# actuatorBoard_2.net
KiCad netlist of a schematic drawn in EAGLE
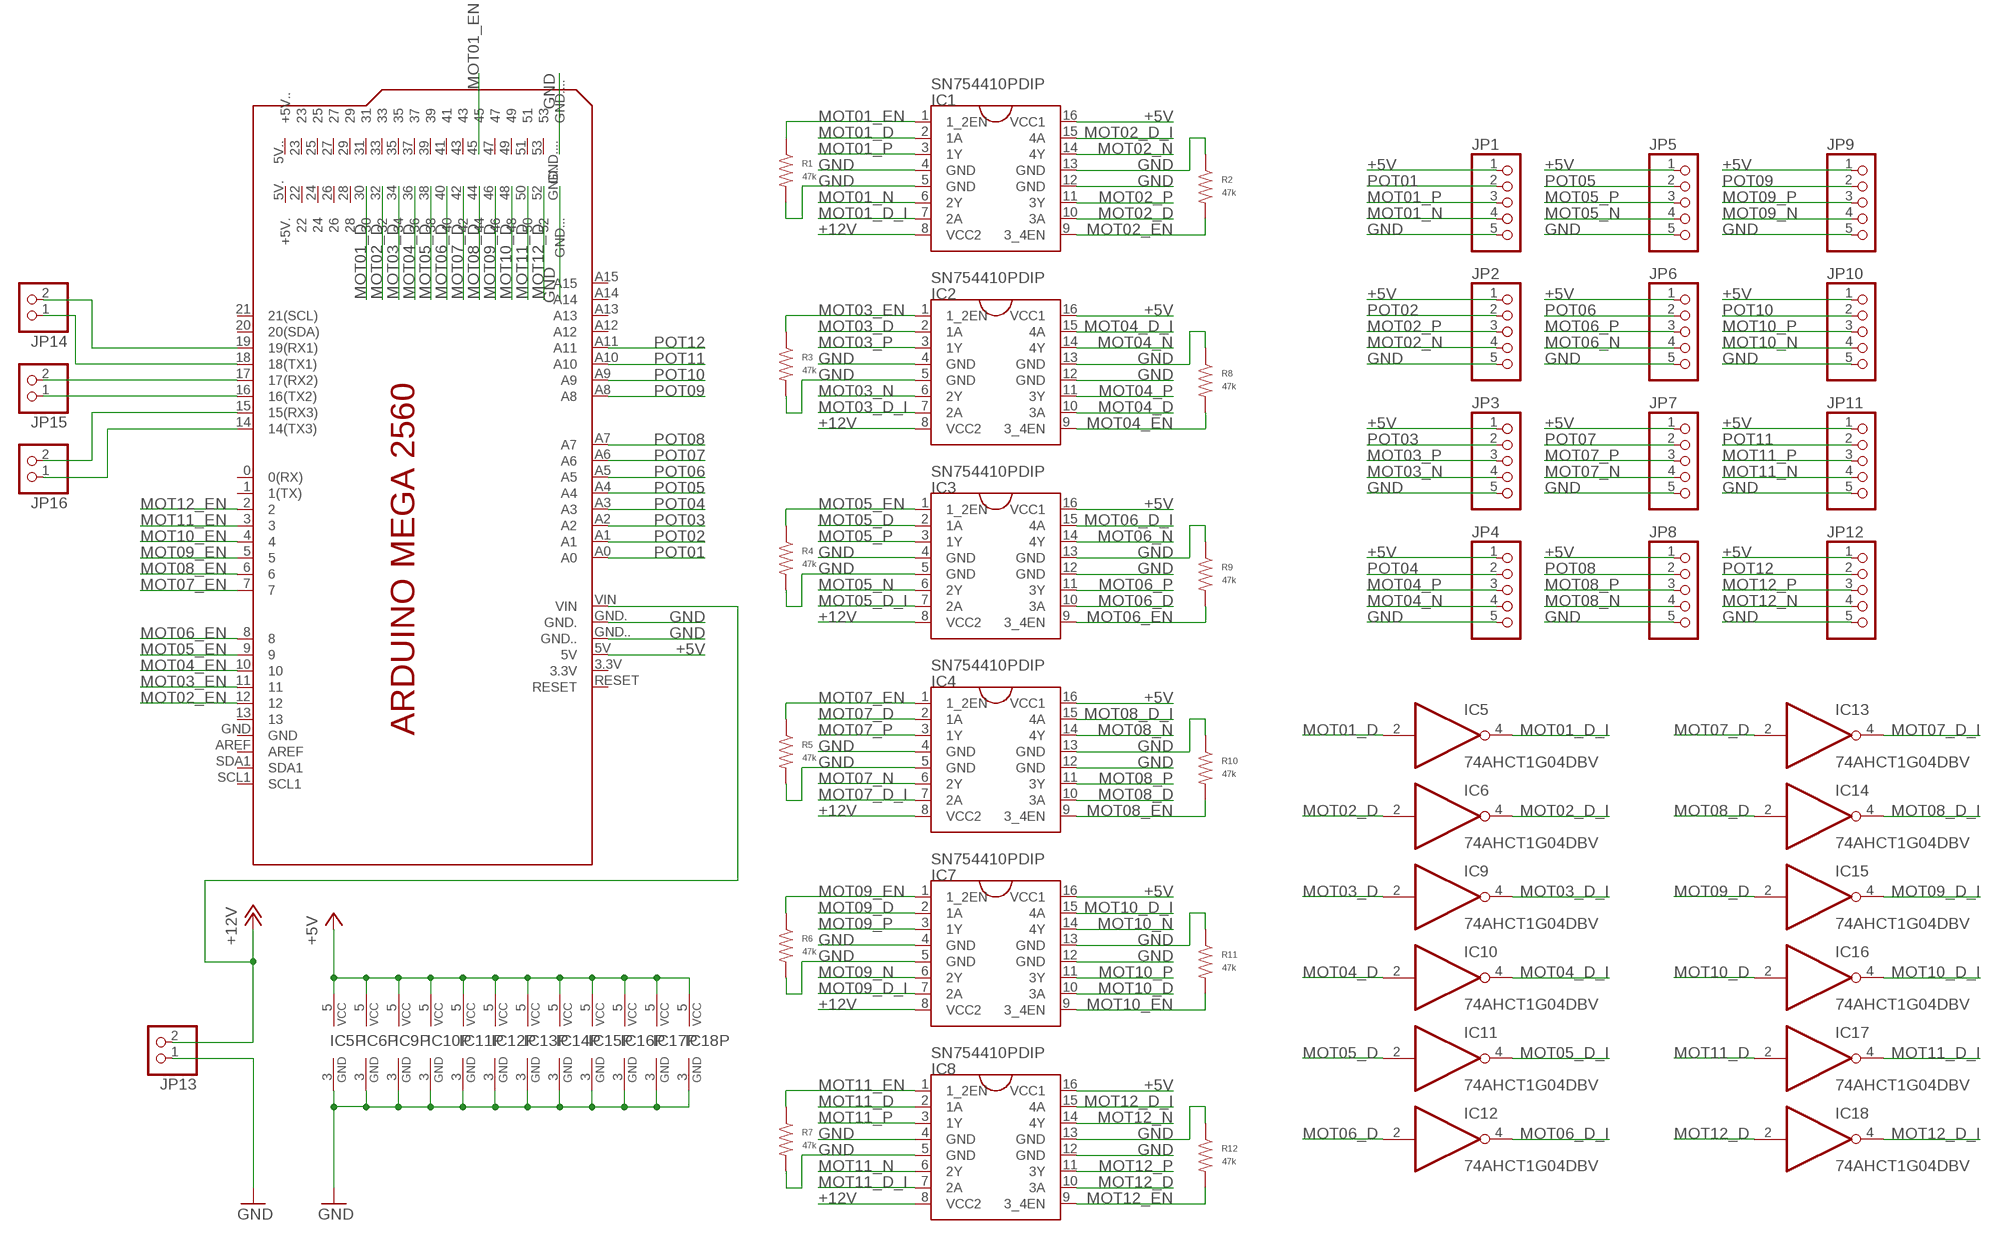
[diagram p0: schematic, sheet 1]

(export (version "E")
  (design (tool "Eeschema 10.0.6"))
  (components
    (comp (ref "IC1")
      (value "SN754410PDIP")
      (footprint "eagle-import:DIL16")
      (libsource (lib "eagle-import") (part "SN754410PDIP"))
    )
    (comp (ref "IC2")
      (value "SN754410PDIP")
      (footprint "eagle-import:DIL16")
      (libsource (lib "eagle-import") (part "SN754410PDIP"))
    )
    (comp (ref "IC3")
      (value "SN754410PDIP")
      (footprint "eagle-import:DIL16")
      (libsource (lib "eagle-import") (part "SN754410PDIP"))
    )
    (comp (ref "IC4")
      (value "SN754410PDIP")
      (footprint "eagle-import:DIL16")
      (libsource (lib "eagle-import") (part "SN754410PDIP"))
    )
    (comp (ref "IC5")
      (value "74AHCT1G04DBV")
      (footprint "eagle-import:SOT23-5")
      (libsource (lib "eagle-import") (part "741G04DBVAHCT"))
    )
    (comp (ref "IC6")
      (value "74AHCT1G04DBV")
      (footprint "eagle-import:SOT23-5")
      (libsource (lib "eagle-import") (part "741G04DBVAHCT"))
    )
    (comp (ref "IC7")
      (value "SN754410PDIP")
      (footprint "eagle-import:DIL16")
      (libsource (lib "eagle-import") (part "SN754410PDIP"))
    )
    (comp (ref "IC8")
      (value "SN754410PDIP")
      (footprint "eagle-import:DIL16")
      (libsource (lib "eagle-import") (part "SN754410PDIP"))
    )
    (comp (ref "IC9")
      (value "74AHCT1G04DBV")
      (footprint "eagle-import:SOT23-5")
      (libsource (lib "eagle-import") (part "741G04DBVAHCT"))
    )
    (comp (ref "IC10")
      (value "74AHCT1G04DBV")
      (footprint "eagle-import:SOT23-5")
      (libsource (lib "eagle-import") (part "741G04DBVAHCT"))
    )
    (comp (ref "IC11")
      (value "74AHCT1G04DBV")
      (footprint "eagle-import:SOT23-5")
      (libsource (lib "eagle-import") (part "741G04DBVAHCT"))
    )
    (comp (ref "IC12")
      (value "74AHCT1G04DBV")
      (footprint "eagle-import:SOT23-5")
      (libsource (lib "eagle-import") (part "741G04DBVAHCT"))
    )
    (comp (ref "IC13")
      (value "74AHCT1G04DBV")
      (footprint "eagle-import:SOT23-5")
      (libsource (lib "eagle-import") (part "741G04DBVAHCT"))
    )
    (comp (ref "IC14")
      (value "74AHCT1G04DBV")
      (footprint "eagle-import:SOT23-5")
      (libsource (lib "eagle-import") (part "741G04DBVAHCT"))
    )
    (comp (ref "IC15")
      (value "74AHCT1G04DBV")
      (footprint "eagle-import:SOT23-5")
      (libsource (lib "eagle-import") (part "741G04DBVAHCT"))
    )
    (comp (ref "IC16")
      (value "74AHCT1G04DBV")
      (footprint "eagle-import:SOT23-5")
      (libsource (lib "eagle-import") (part "741G04DBVAHCT"))
    )
    (comp (ref "IC17")
      (value "74AHCT1G04DBV")
      (footprint "eagle-import:SOT23-5")
      (libsource (lib "eagle-import") (part "741G04DBVAHCT"))
    )
    (comp (ref "IC18")
      (value "74AHCT1G04DBV")
      (footprint "eagle-import:SOT23-5")
      (libsource (lib "eagle-import") (part "741G04DBVAHCT"))
    )
    (comp (ref "JP1")
      (value "PINHD-1X5")
      (footprint "eagle-import:1X05")
      (libsource (lib "eagle-import") (part "PINHD-1X5"))
    )
    (comp (ref "JP2")
      (value "PINHD-1X5")
      (footprint "eagle-import:1X05")
      (libsource (lib "eagle-import") (part "PINHD-1X5"))
    )
    (comp (ref "JP3")
      (value "PINHD-1X5")
      (footprint "eagle-import:1X05")
      (libsource (lib "eagle-import") (part "PINHD-1X5"))
    )
    (comp (ref "JP4")
      (value "PINHD-1X5")
      (footprint "eagle-import:1X05")
      (libsource (lib "eagle-import") (part "PINHD-1X5"))
    )
    (comp (ref "JP5")
      (value "PINHD-1X5")
      (footprint "eagle-import:1X05")
      (libsource (lib "eagle-import") (part "PINHD-1X5"))
    )
    (comp (ref "JP6")
      (value "PINHD-1X5")
      (footprint "eagle-import:1X05")
      (libsource (lib "eagle-import") (part "PINHD-1X5"))
    )
    (comp (ref "JP7")
      (value "PINHD-1X5")
      (footprint "eagle-import:1X05")
      (libsource (lib "eagle-import") (part "PINHD-1X5"))
    )
    (comp (ref "JP8")
      (value "PINHD-1X5")
      (footprint "eagle-import:1X05")
      (libsource (lib "eagle-import") (part "PINHD-1X5"))
    )
    (comp (ref "JP9")
      (value "PINHD-1X5")
      (footprint "eagle-import:1X05")
      (libsource (lib "eagle-import") (part "PINHD-1X5"))
    )
    (comp (ref "JP10")
      (value "PINHD-1X5")
      (footprint "eagle-import:1X05")
      (libsource (lib "eagle-import") (part "PINHD-1X5"))
    )
    (comp (ref "JP11")
      (value "PINHD-1X5")
      (footprint "eagle-import:1X05")
      (libsource (lib "eagle-import") (part "PINHD-1X5"))
    )
    (comp (ref "JP12")
      (value "PINHD-1X5")
      (footprint "eagle-import:1X05")
      (libsource (lib "eagle-import") (part "PINHD-1X5"))
    )
    (comp (ref "JP13")
      (value "PINHD-1X2")
      (footprint "eagle-import:1X02")
      (libsource (lib "eagle-import") (part "PINHD-1X2"))
    )
    (comp (ref "JP14")
      (value "PINHD-1X2")
      (footprint "eagle-import:1X02")
      (libsource (lib "eagle-import") (part "PINHD-1X2"))
    )
    (comp (ref "JP15")
      (value "PINHD-1X2")
      (footprint "eagle-import:1X02")
      (libsource (lib "eagle-import") (part "PINHD-1X2"))
    )
    (comp (ref "JP16")
      (value "PINHD-1X2")
      (footprint "eagle-import:1X02")
      (libsource (lib "eagle-import") (part "PINHD-1X2"))
    )
    (comp (ref "PCB1")
      (value "ARDUINO_MEGA2560")
      (footprint "eagle-import:ARDUINO_MEGA2560")
      (libsource (lib "eagle-import") (part "ARDUINO_MEGA2560"))
    )
    (comp (ref "R1")
      (value "47k")
      (footprint "eagle-import:R0603")
      (libsource (lib "eagle-import") (part "RESISTOR_0603"))
    )
    (comp (ref "R2")
      (value "47k")
      (footprint "eagle-import:R0603")
      (libsource (lib "eagle-import") (part "RESISTOR_0603"))
    )
    (comp (ref "R3")
      (value "47k")
      (footprint "eagle-import:R0603")
      (libsource (lib "eagle-import") (part "RESISTOR_0603"))
    )
    (comp (ref "R4")
      (value "47k")
      (footprint "eagle-import:R0603")
      (libsource (lib "eagle-import") (part "RESISTOR_0603"))
    )
    (comp (ref "R5")
      (value "47k")
      (footprint "eagle-import:R0603")
      (libsource (lib "eagle-import") (part "RESISTOR_0603"))
    )
    (comp (ref "R6")
      (value "47k")
      (footprint "eagle-import:R0603")
      (libsource (lib "eagle-import") (part "RESISTOR_0603"))
    )
    (comp (ref "R7")
      (value "47k")
      (footprint "eagle-import:R0603")
      (libsource (lib "eagle-import") (part "RESISTOR_0603"))
    )
    (comp (ref "R8")
      (value "47k")
      (footprint "eagle-import:R0603")
      (libsource (lib "eagle-import") (part "RESISTOR_0603"))
    )
    (comp (ref "R9")
      (value "47k")
      (footprint "eagle-import:R0603")
      (libsource (lib "eagle-import") (part "RESISTOR_0603"))
    )
    (comp (ref "R10")
      (value "47k")
      (footprint "eagle-import:R0603")
      (libsource (lib "eagle-import") (part "RESISTOR_0603"))
    )
    (comp (ref "R11")
      (value "47k")
      (footprint "eagle-import:R0603")
      (libsource (lib "eagle-import") (part "RESISTOR_0603"))
    )
    (comp (ref "R12")
      (value "47k")
      (footprint "eagle-import:R0603")
      (libsource (lib "eagle-import") (part "RESISTOR_0603"))
    )
  )
  (nets
    (net (code "1") (name "+5V") (class "Default")
      (node (ref "IC1") (pin "16") (pinfunction "VCC1_16") (pintype "bidirectional"))
      (node (ref "IC10") (pin "5") (pinfunction "VCC_5") (pintype "power_in"))
      (node (ref "IC11") (pin "5") (pinfunction "VCC_5") (pintype "power_in"))
      (node (ref "IC12") (pin "5") (pinfunction "VCC_5") (pintype "power_in"))
      (node (ref "IC13") (pin "5") (pinfunction "VCC_5") (pintype "power_in"))
      (node (ref "IC14") (pin "5") (pinfunction "VCC_5") (pintype "power_in"))
      (node (ref "IC15") (pin "5") (pinfunction "VCC_5") (pintype "power_in"))
      (node (ref "IC16") (pin "5") (pinfunction "VCC_5") (pintype "power_in"))
      (node (ref "IC17") (pin "5") (pinfunction "VCC_5") (pintype "power_in"))
      (node (ref "IC18") (pin "5") (pinfunction "VCC_5") (pintype "power_in"))
      (node (ref "IC2") (pin "16") (pinfunction "VCC1_16") (pintype "bidirectional"))
      (node (ref "IC3") (pin "16") (pinfunction "VCC1_16") (pintype "bidirectional"))
      (node (ref "IC4") (pin "16") (pinfunction "VCC1_16") (pintype "bidirectional"))
      (node (ref "IC5") (pin "5") (pinfunction "VCC_5") (pintype "power_in"))
      (node (ref "IC6") (pin "5") (pinfunction "VCC_5") (pintype "power_in"))
      (node (ref "IC7") (pin "16") (pinfunction "VCC1_16") (pintype "bidirectional"))
      (node (ref "IC8") (pin "16") (pinfunction "VCC1_16") (pintype "bidirectional"))
      (node (ref "IC9") (pin "5") (pinfunction "VCC_5") (pintype "power_in"))
      (node (ref "JP1") (pin "1") (pinfunction "1_1") (pintype "passive"))
      (node (ref "JP10") (pin "1") (pinfunction "1_1") (pintype "passive"))
      (node (ref "JP11") (pin "1") (pinfunction "1_1") (pintype "passive"))
      (node (ref "JP12") (pin "1") (pinfunction "1_1") (pintype "passive"))
      (node (ref "JP2") (pin "1") (pinfunction "1_1") (pintype "passive"))
      (node (ref "JP3") (pin "1") (pinfunction "1_1") (pintype "passive"))
      (node (ref "JP4") (pin "1") (pinfunction "1_1") (pintype "passive"))
      (node (ref "JP5") (pin "1") (pinfunction "1_1") (pintype "passive"))
      (node (ref "JP6") (pin "1") (pinfunction "1_1") (pintype "passive"))
      (node (ref "JP7") (pin "1") (pinfunction "1_1") (pintype "passive"))
      (node (ref "JP8") (pin "1") (pinfunction "1_1") (pintype "passive"))
      (node (ref "JP9") (pin "1") (pinfunction "1_1") (pintype "passive"))
      (node (ref "PCB1") (pin "5V") (pinfunction "5V_5V") (pintype "bidirectional"))
    )
    (net (code "2") (name "+12V") (class "Default")
      (node (ref "IC1") (pin "8") (pinfunction "VCC2_8") (pintype "bidirectional"))
      (node (ref "IC2") (pin "8") (pinfunction "VCC2_8") (pintype "bidirectional"))
      (node (ref "IC3") (pin "8") (pinfunction "VCC2_8") (pintype "bidirectional"))
      (node (ref "IC4") (pin "8") (pinfunction "VCC2_8") (pintype "bidirectional"))
      (node (ref "IC7") (pin "8") (pinfunction "VCC2_8") (pintype "bidirectional"))
      (node (ref "IC8") (pin "8") (pinfunction "VCC2_8") (pintype "bidirectional"))
      (node (ref "JP13") (pin "2") (pinfunction "2_2") (pintype "passive"))
      (node (ref "PCB1") (pin "VIN") (pinfunction "VIN_VIN") (pintype "bidirectional"))
    )
    (net (code "3") (name "/MOT01_D") (class "Default")
      (node (ref "IC1") (pin "2") (pinfunction "1A_2") (pintype "bidirectional"))
      (node (ref "IC5") (pin "2") (pinfunction "I_2") (pintype "input"))
      (node (ref "PCB1") (pin "30") (pinfunction "30_30") (pintype "bidirectional"))
    )
    (net (code "4") (name "/MOT01_D_I") (class "Default")
      (node (ref "IC1") (pin "7") (pinfunction "2A_7") (pintype "bidirectional"))
      (node (ref "IC5") (pin "4") (pinfunction "O_4") (pintype "output"))
    )
    (net (code "5") (name "/MOT01_EN") (class "Default")
      (node (ref "IC1") (pin "1") (pinfunction "1_2EN_1") (pintype "bidirectional"))
      (node (ref "PCB1") (pin "45") (pinfunction "45_45") (pintype "bidirectional"))
      (node (ref "R1") (pin "P$1") (pinfunction "P$1_P$1") (pintype "passive"))
    )
    (net (code "6") (name "/MOT01_N") (class "Default")
      (node (ref "IC1") (pin "6") (pinfunction "2Y_6") (pintype "bidirectional"))
      (node (ref "JP1") (pin "4") (pinfunction "4_4") (pintype "passive"))
    )
    (net (code "7") (name "/MOT01_P") (class "Default")
      (node (ref "IC1") (pin "3") (pinfunction "1Y_3") (pintype "bidirectional"))
      (node (ref "JP1") (pin "3") (pinfunction "3_3") (pintype "passive"))
    )
    (net (code "8") (name "/MOT02_D") (class "Default")
      (node (ref "IC1") (pin "10") (pinfunction "3A_10") (pintype "bidirectional"))
      (node (ref "IC6") (pin "2") (pinfunction "I_2") (pintype "input"))
      (node (ref "PCB1") (pin "32") (pinfunction "32_32") (pintype "bidirectional"))
    )
    (net (code "9") (name "/MOT02_D_I") (class "Default")
      (node (ref "IC1") (pin "15") (pinfunction "4A_15") (pintype "bidirectional"))
      (node (ref "IC6") (pin "4") (pinfunction "O_4") (pintype "output"))
    )
    (net (code "10") (name "/MOT02_EN") (class "Default")
      (node (ref "IC1") (pin "9") (pinfunction "3_4EN_9") (pintype "bidirectional"))
      (node (ref "PCB1") (pin "12") (pinfunction "12_12") (pintype "bidirectional"))
      (node (ref "R2") (pin "P$2") (pinfunction "P$2_P$2") (pintype "passive"))
    )
    (net (code "11") (name "/MOT02_N") (class "Default")
      (node (ref "IC1") (pin "14") (pinfunction "4Y_14") (pintype "bidirectional"))
      (node (ref "JP2") (pin "4") (pinfunction "4_4") (pintype "passive"))
    )
    (net (code "12") (name "/MOT02_P") (class "Default")
      (node (ref "IC1") (pin "11") (pinfunction "3Y_11") (pintype "bidirectional"))
      (node (ref "JP2") (pin "3") (pinfunction "3_3") (pintype "passive"))
    )
    (net (code "13") (name "/MOT03_D") (class "Default")
      (node (ref "IC2") (pin "2") (pinfunction "1A_2") (pintype "bidirectional"))
      (node (ref "IC9") (pin "2") (pinfunction "I_2") (pintype "input"))
      (node (ref "PCB1") (pin "34") (pinfunction "34_34") (pintype "bidirectional"))
    )
    (net (code "14") (name "/MOT03_D_I") (class "Default")
      (node (ref "IC2") (pin "7") (pinfunction "2A_7") (pintype "bidirectional"))
      (node (ref "IC9") (pin "4") (pinfunction "O_4") (pintype "output"))
    )
    (net (code "15") (name "/MOT03_EN") (class "Default")
      (node (ref "IC2") (pin "1") (pinfunction "1_2EN_1") (pintype "bidirectional"))
      (node (ref "PCB1") (pin "11") (pinfunction "11_11") (pintype "bidirectional"))
      (node (ref "R3") (pin "P$1") (pinfunction "P$1_P$1") (pintype "passive"))
    )
    (net (code "16") (name "/MOT03_N") (class "Default")
      (node (ref "IC2") (pin "6") (pinfunction "2Y_6") (pintype "bidirectional"))
      (node (ref "JP3") (pin "4") (pinfunction "4_4") (pintype "passive"))
    )
    (net (code "17") (name "/MOT03_P") (class "Default")
      (node (ref "IC2") (pin "3") (pinfunction "1Y_3") (pintype "bidirectional"))
      (node (ref "JP3") (pin "3") (pinfunction "3_3") (pintype "passive"))
    )
    (net (code "18") (name "/MOT04_D") (class "Default")
      (node (ref "IC10") (pin "2") (pinfunction "I_2") (pintype "input"))
      (node (ref "IC2") (pin "10") (pinfunction "3A_10") (pintype "bidirectional"))
      (node (ref "PCB1") (pin "36") (pinfunction "36_36") (pintype "bidirectional"))
    )
    (net (code "19") (name "/MOT04_D_I") (class "Default")
      (node (ref "IC10") (pin "4") (pinfunction "O_4") (pintype "output"))
      (node (ref "IC2") (pin "15") (pinfunction "4A_15") (pintype "bidirectional"))
    )
    (net (code "20") (name "/MOT04_EN") (class "Default")
      (node (ref "IC2") (pin "9") (pinfunction "3_4EN_9") (pintype "bidirectional"))
      (node (ref "PCB1") (pin "10") (pinfunction "10_10") (pintype "bidirectional"))
      (node (ref "R8") (pin "P$2") (pinfunction "P$2_P$2") (pintype "passive"))
    )
    (net (code "21") (name "/MOT04_N") (class "Default")
      (node (ref "IC2") (pin "14") (pinfunction "4Y_14") (pintype "bidirectional"))
      (node (ref "JP4") (pin "4") (pinfunction "4_4") (pintype "passive"))
    )
    (net (code "22") (name "/MOT04_P") (class "Default")
      (node (ref "IC2") (pin "11") (pinfunction "3Y_11") (pintype "bidirectional"))
      (node (ref "JP4") (pin "3") (pinfunction "3_3") (pintype "passive"))
    )
    (net (code "23") (name "/MOT05_D") (class "Default")
      (node (ref "IC11") (pin "2") (pinfunction "I_2") (pintype "input"))
      (node (ref "IC3") (pin "2") (pinfunction "1A_2") (pintype "bidirectional"))
      (node (ref "PCB1") (pin "38") (pinfunction "38_38") (pintype "bidirectional"))
    )
    (net (code "24") (name "/MOT05_D_I") (class "Default")
      (node (ref "IC11") (pin "4") (pinfunction "O_4") (pintype "output"))
      (node (ref "IC3") (pin "7") (pinfunction "2A_7") (pintype "bidirectional"))
    )
    (net (code "25") (name "/MOT05_EN") (class "Default")
      (node (ref "IC3") (pin "1") (pinfunction "1_2EN_1") (pintype "bidirectional"))
      (node (ref "PCB1") (pin "9") (pinfunction "9_9") (pintype "bidirectional"))
      (node (ref "R4") (pin "P$1") (pinfunction "P$1_P$1") (pintype "passive"))
    )
    (net (code "26") (name "/MOT05_N") (class "Default")
      (node (ref "IC3") (pin "6") (pinfunction "2Y_6") (pintype "bidirectional"))
      (node (ref "JP5") (pin "4") (pinfunction "4_4") (pintype "passive"))
    )
    (net (code "27") (name "/MOT05_P") (class "Default")
      (node (ref "IC3") (pin "3") (pinfunction "1Y_3") (pintype "bidirectional"))
      (node (ref "JP5") (pin "3") (pinfunction "3_3") (pintype "passive"))
    )
    (net (code "28") (name "/MOT06_D") (class "Default")
      (node (ref "IC12") (pin "2") (pinfunction "I_2") (pintype "input"))
      (node (ref "IC3") (pin "10") (pinfunction "3A_10") (pintype "bidirectional"))
      (node (ref "PCB1") (pin "40") (pinfunction "40_40") (pintype "bidirectional"))
    )
    (net (code "29") (name "/MOT06_D_I") (class "Default")
      (node (ref "IC12") (pin "4") (pinfunction "O_4") (pintype "output"))
      (node (ref "IC3") (pin "15") (pinfunction "4A_15") (pintype "bidirectional"))
    )
    (net (code "30") (name "/MOT06_EN") (class "Default")
      (node (ref "IC3") (pin "9") (pinfunction "3_4EN_9") (pintype "bidirectional"))
      (node (ref "PCB1") (pin "8") (pinfunction "8_8") (pintype "bidirectional"))
      (node (ref "R9") (pin "P$2") (pinfunction "P$2_P$2") (pintype "passive"))
    )
    (net (code "31") (name "/MOT06_N") (class "Default")
      (node (ref "IC3") (pin "14") (pinfunction "4Y_14") (pintype "bidirectional"))
      (node (ref "JP6") (pin "4") (pinfunction "4_4") (pintype "passive"))
    )
    (net (code "32") (name "/MOT06_P") (class "Default")
      (node (ref "IC3") (pin "11") (pinfunction "3Y_11") (pintype "bidirectional"))
      (node (ref "JP6") (pin "3") (pinfunction "3_3") (pintype "passive"))
    )
    (net (code "33") (name "/MOT07_D") (class "Default")
      (node (ref "IC13") (pin "2") (pinfunction "I_2") (pintype "input"))
      (node (ref "IC4") (pin "2") (pinfunction "1A_2") (pintype "bidirectional"))
      (node (ref "PCB1") (pin "42") (pinfunction "42_42") (pintype "bidirectional"))
    )
    (net (code "34") (name "/MOT07_D_I") (class "Default")
      (node (ref "IC13") (pin "4") (pinfunction "O_4") (pintype "output"))
      (node (ref "IC4") (pin "7") (pinfunction "2A_7") (pintype "bidirectional"))
    )
    (net (code "35") (name "/MOT07_EN") (class "Default")
      (node (ref "IC4") (pin "1") (pinfunction "1_2EN_1") (pintype "bidirectional"))
      (node (ref "PCB1") (pin "7") (pinfunction "7_7") (pintype "bidirectional"))
      (node (ref "R5") (pin "P$1") (pinfunction "P$1_P$1") (pintype "passive"))
    )
    (net (code "36") (name "/MOT07_N") (class "Default")
      (node (ref "IC4") (pin "6") (pinfunction "2Y_6") (pintype "bidirectional"))
      (node (ref "JP7") (pin "4") (pinfunction "4_4") (pintype "passive"))
    )
    (net (code "37") (name "/MOT07_P") (class "Default")
      (node (ref "IC4") (pin "3") (pinfunction "1Y_3") (pintype "bidirectional"))
      (node (ref "JP7") (pin "3") (pinfunction "3_3") (pintype "passive"))
    )
    (net (code "38") (name "/MOT08_D") (class "Default")
      (node (ref "IC14") (pin "2") (pinfunction "I_2") (pintype "input"))
      (node (ref "IC4") (pin "10") (pinfunction "3A_10") (pintype "bidirectional"))
      (node (ref "PCB1") (pin "44") (pinfunction "44_44") (pintype "bidirectional"))
    )
    (net (code "39") (name "/MOT08_D_I") (class "Default")
      (node (ref "IC14") (pin "4") (pinfunction "O_4") (pintype "output"))
      (node (ref "IC4") (pin "15") (pinfunction "4A_15") (pintype "bidirectional"))
    )
    (net (code "40") (name "/MOT08_EN") (class "Default")
      (node (ref "IC4") (pin "9") (pinfunction "3_4EN_9") (pintype "bidirectional"))
      (node (ref "PCB1") (pin "6") (pinfunction "6_6") (pintype "bidirectional"))
      (node (ref "R10") (pin "P$2") (pinfunction "P$2_P$2") (pintype "passive"))
    )
    (net (code "41") (name "/MOT08_N") (class "Default")
      (node (ref "IC4") (pin "14") (pinfunction "4Y_14") (pintype "bidirectional"))
      (node (ref "JP8") (pin "4") (pinfunction "4_4") (pintype "passive"))
    )
    (net (code "42") (name "/MOT08_P") (class "Default")
      (node (ref "IC4") (pin "11") (pinfunction "3Y_11") (pintype "bidirectional"))
      (node (ref "JP8") (pin "3") (pinfunction "3_3") (pintype "passive"))
    )
    (net (code "43") (name "/MOT09_D") (class "Default")
      (node (ref "IC15") (pin "2") (pinfunction "I_2") (pintype "input"))
      (node (ref "IC7") (pin "2") (pinfunction "1A_2") (pintype "bidirectional"))
      (node (ref "PCB1") (pin "46") (pinfunction "46_46") (pintype "bidirectional"))
    )
    (net (code "44") (name "/MOT09_D_I") (class "Default")
      (node (ref "IC15") (pin "4") (pinfunction "O_4") (pintype "output"))
      (node (ref "IC7") (pin "7") (pinfunction "2A_7") (pintype "bidirectional"))
    )
    (net (code "45") (name "/MOT09_EN") (class "Default")
      (node (ref "IC7") (pin "1") (pinfunction "1_2EN_1") (pintype "bidirectional"))
      (node (ref "PCB1") (pin "5") (pinfunction "5_5") (pintype "bidirectional"))
      (node (ref "R6") (pin "P$1") (pinfunction "P$1_P$1") (pintype "passive"))
    )
    (net (code "46") (name "/MOT09_N") (class "Default")
      (node (ref "IC7") (pin "6") (pinfunction "2Y_6") (pintype "bidirectional"))
      (node (ref "JP9") (pin "4") (pinfunction "4_4") (pintype "passive"))
    )
    (net (code "47") (name "/MOT09_P") (class "Default")
      (node (ref "IC7") (pin "3") (pinfunction "1Y_3") (pintype "bidirectional"))
      (node (ref "JP9") (pin "3") (pinfunction "3_3") (pintype "passive"))
    )
    (net (code "48") (name "/MOT10_D") (class "Default")
      (node (ref "IC16") (pin "2") (pinfunction "I_2") (pintype "input"))
      (node (ref "IC7") (pin "10") (pinfunction "3A_10") (pintype "bidirectional"))
      (node (ref "PCB1") (pin "48") (pinfunction "48_48") (pintype "bidirectional"))
    )
    (net (code "49") (name "/MOT10_D_I") (class "Default")
      (node (ref "IC16") (pin "4") (pinfunction "O_4") (pintype "output"))
      (node (ref "IC7") (pin "15") (pinfunction "4A_15") (pintype "bidirectional"))
    )
    (net (code "50") (name "/MOT10_EN") (class "Default")
      (node (ref "IC7") (pin "9") (pinfunction "3_4EN_9") (pintype "bidirectional"))
      (node (ref "PCB1") (pin "4") (pinfunction "4_4") (pintype "bidirectional"))
      (node (ref "R11") (pin "P$2") (pinfunction "P$2_P$2") (pintype "passive"))
    )
    (net (code "51") (name "/MOT10_N") (class "Default")
      (node (ref "IC7") (pin "14") (pinfunction "4Y_14") (pintype "bidirectional"))
      (node (ref "JP10") (pin "4") (pinfunction "4_4") (pintype "passive"))
    )
    (net (code "52") (name "/MOT10_P") (class "Default")
      (node (ref "IC7") (pin "11") (pinfunction "3Y_11") (pintype "bidirectional"))
      (node (ref "JP10") (pin "3") (pinfunction "3_3") (pintype "passive"))
    )
    (net (code "53") (name "/MOT11_D") (class "Default")
      (node (ref "IC17") (pin "2") (pinfunction "I_2") (pintype "input"))
      (node (ref "IC8") (pin "2") (pinfunction "1A_2") (pintype "bidirectional"))
      (node (ref "PCB1") (pin "50") (pinfunction "50_50") (pintype "bidirectional"))
    )
    (net (code "54") (name "/MOT11_D_I") (class "Default")
      (node (ref "IC17") (pin "4") (pinfunction "O_4") (pintype "output"))
      (node (ref "IC8") (pin "7") (pinfunction "2A_7") (pintype "bidirectional"))
    )
    (net (code "55") (name "/MOT11_EN") (class "Default")
      (node (ref "IC8") (pin "1") (pinfunction "1_2EN_1") (pintype "bidirectional"))
      (node (ref "PCB1") (pin "3") (pinfunction "3_3") (pintype "bidirectional"))
      (node (ref "R7") (pin "P$1") (pinfunction "P$1_P$1") (pintype "passive"))
    )
    (net (code "56") (name "/MOT11_N") (class "Default")
      (node (ref "IC8") (pin "6") (pinfunction "2Y_6") (pintype "bidirectional"))
      (node (ref "JP11") (pin "4") (pinfunction "4_4") (pintype "passive"))
    )
    (net (code "57") (name "/MOT11_P") (class "Default")
      (node (ref "IC8") (pin "3") (pinfunction "1Y_3") (pintype "bidirectional"))
      (node (ref "JP11") (pin "3") (pinfunction "3_3") (pintype "passive"))
    )
    (net (code "58") (name "/MOT12_D") (class "Default")
      (node (ref "IC18") (pin "2") (pinfunction "I_2") (pintype "input"))
      (node (ref "IC8") (pin "10") (pinfunction "3A_10") (pintype "bidirectional"))
      (node (ref "PCB1") (pin "52") (pinfunction "52_52") (pintype "bidirectional"))
    )
    (net (code "59") (name "/MOT12_D_I") (class "Default")
      (node (ref "IC18") (pin "4") (pinfunction "O_4") (pintype "output"))
      (node (ref "IC8") (pin "15") (pinfunction "4A_15") (pintype "bidirectional"))
    )
    (net (code "60") (name "/MOT12_EN") (class "Default")
      (node (ref "IC8") (pin "9") (pinfunction "3_4EN_9") (pintype "bidirectional"))
      (node (ref "PCB1") (pin "2") (pinfunction "2_2") (pintype "bidirectional"))
      (node (ref "R12") (pin "P$2") (pinfunction "P$2_P$2") (pintype "passive"))
    )
    (net (code "61") (name "/MOT12_N") (class "Default")
      (node (ref "IC8") (pin "14") (pinfunction "4Y_14") (pintype "bidirectional"))
      (node (ref "JP12") (pin "4") (pinfunction "4_4") (pintype "passive"))
    )
    (net (code "62") (name "/MOT12_P") (class "Default")
      (node (ref "IC8") (pin "11") (pinfunction "3Y_11") (pintype "bidirectional"))
      (node (ref "JP12") (pin "3") (pinfunction "3_3") (pintype "passive"))
    )
    (net (code "63") (name "/POT01") (class "Default")
      (node (ref "JP1") (pin "2") (pinfunction "2_2") (pintype "passive"))
      (node (ref "PCB1") (pin "A0") (pinfunction "A0_A0") (pintype "bidirectional"))
    )
    (net (code "64") (name "/POT02") (class "Default")
      (node (ref "JP2") (pin "2") (pinfunction "2_2") (pintype "passive"))
      (node (ref "PCB1") (pin "A1") (pinfunction "A1_A1") (pintype "bidirectional"))
    )
    (net (code "65") (name "/POT03") (class "Default")
      (node (ref "JP3") (pin "2") (pinfunction "2_2") (pintype "passive"))
      (node (ref "PCB1") (pin "A2") (pinfunction "A2_A2") (pintype "bidirectional"))
    )
    (net (code "66") (name "/POT04") (class "Default")
      (node (ref "JP4") (pin "2") (pinfunction "2_2") (pintype "passive"))
      (node (ref "PCB1") (pin "A3") (pinfunction "A3_A3") (pintype "bidirectional"))
    )
    (net (code "67") (name "/POT05") (class "Default")
      (node (ref "JP5") (pin "2") (pinfunction "2_2") (pintype "passive"))
      (node (ref "PCB1") (pin "A4") (pinfunction "A4_A4") (pintype "bidirectional"))
    )
    (net (code "68") (name "/POT06") (class "Default")
      (node (ref "JP6") (pin "2") (pinfunction "2_2") (pintype "passive"))
      (node (ref "PCB1") (pin "A5") (pinfunction "A5_A5") (pintype "bidirectional"))
    )
    (net (code "69") (name "/POT07") (class "Default")
      (node (ref "JP7") (pin "2") (pinfunction "2_2") (pintype "passive"))
      (node (ref "PCB1") (pin "A6") (pinfunction "A6_A6") (pintype "bidirectional"))
    )
    (net (code "70") (name "/POT08") (class "Default")
      (node (ref "JP8") (pin "2") (pinfunction "2_2") (pintype "passive"))
      (node (ref "PCB1") (pin "A7") (pinfunction "A7_A7") (pintype "bidirectional"))
    )
    (net (code "71") (name "/POT09") (class "Default")
      (node (ref "JP9") (pin "2") (pinfunction "2_2") (pintype "passive"))
      (node (ref "PCB1") (pin "A8") (pinfunction "A8_A8") (pintype "bidirectional"))
    )
    (net (code "72") (name "/POT10") (class "Default")
      (node (ref "JP10") (pin "2") (pinfunction "2_2") (pintype "passive"))
      (node (ref "PCB1") (pin "A9") (pinfunction "A9_A9") (pintype "bidirectional"))
    )
    (net (code "73") (name "/POT11") (class "Default")
      (node (ref "JP11") (pin "2") (pinfunction "2_2") (pintype "passive"))
      (node (ref "PCB1") (pin "A10") (pinfunction "A10_A10") (pintype "bidirectional"))
    )
    (net (code "74") (name "/POT12") (class "Default")
      (node (ref "JP12") (pin "2") (pinfunction "2_2") (pintype "passive"))
      (node (ref "PCB1") (pin "A11") (pinfunction "A11_A11") (pintype "bidirectional"))
    )
    (net (code "75") (name "GND") (class "Default")
      (node (ref "IC1") (pin "12") (pinfunction "GND_12") (pintype "bidirectional"))
      (node (ref "IC1") (pin "13") (pinfunction "GND_13") (pintype "bidirectional"))
      (node (ref "IC1") (pin "4") (pinfunction "GND_4") (pintype "bidirectional"))
      (node (ref "IC1") (pin "5") (pinfunction "GND_5") (pintype "bidirectional"))
      (node (ref "IC10") (pin "3") (pinfunction "GND_3") (pintype "power_in"))
      (node (ref "IC11") (pin "3") (pinfunction "GND_3") (pintype "power_in"))
      (node (ref "IC12") (pin "3") (pinfunction "GND_3") (pintype "power_in"))
      (node (ref "IC13") (pin "3") (pinfunction "GND_3") (pintype "power_in"))
      (node (ref "IC14") (pin "3") (pinfunction "GND_3") (pintype "power_in"))
      (node (ref "IC15") (pin "3") (pinfunction "GND_3") (pintype "power_in"))
      (node (ref "IC16") (pin "3") (pinfunction "GND_3") (pintype "power_in"))
      (node (ref "IC17") (pin "3") (pinfunction "GND_3") (pintype "power_in"))
      (node (ref "IC18") (pin "3") (pinfunction "GND_3") (pintype "power_in"))
      (node (ref "IC2") (pin "12") (pinfunction "GND_12") (pintype "bidirectional"))
      (node (ref "IC2") (pin "13") (pinfunction "GND_13") (pintype "bidirectional"))
      (node (ref "IC2") (pin "4") (pinfunction "GND_4") (pintype "bidirectional"))
      (node (ref "IC2") (pin "5") (pinfunction "GND_5") (pintype "bidirectional"))
      (node (ref "IC3") (pin "12") (pinfunction "GND_12") (pintype "bidirectional"))
      (node (ref "IC3") (pin "13") (pinfunction "GND_13") (pintype "bidirectional"))
      (node (ref "IC3") (pin "4") (pinfunction "GND_4") (pintype "bidirectional"))
      (node (ref "IC3") (pin "5") (pinfunction "GND_5") (pintype "bidirectional"))
      (node (ref "IC4") (pin "12") (pinfunction "GND_12") (pintype "bidirectional"))
      (node (ref "IC4") (pin "13") (pinfunction "GND_13") (pintype "bidirectional"))
      (node (ref "IC4") (pin "4") (pinfunction "GND_4") (pintype "bidirectional"))
      (node (ref "IC4") (pin "5") (pinfunction "GND_5") (pintype "bidirectional"))
      (node (ref "IC5") (pin "3") (pinfunction "GND_3") (pintype "power_in"))
      (node (ref "IC6") (pin "3") (pinfunction "GND_3") (pintype "power_in"))
      (node (ref "IC7") (pin "12") (pinfunction "GND_12") (pintype "bidirectional"))
      (node (ref "IC7") (pin "13") (pinfunction "GND_13") (pintype "bidirectional"))
      (node (ref "IC7") (pin "4") (pinfunction "GND_4") (pintype "bidirectional"))
      (node (ref "IC7") (pin "5") (pinfunction "GND_5") (pintype "bidirectional"))
      (node (ref "IC8") (pin "12") (pinfunction "GND_12") (pintype "bidirectional"))
      (node (ref "IC8") (pin "13") (pinfunction "GND_13") (pintype "bidirectional"))
      (node (ref "IC8") (pin "4") (pinfunction "GND_4") (pintype "bidirectional"))
      (node (ref "IC8") (pin "5") (pinfunction "GND_5") (pintype "bidirectional"))
      (node (ref "IC9") (pin "3") (pinfunction "GND_3") (pintype "power_in"))
      (node (ref "JP1") (pin "5") (pinfunction "5_5") (pintype "passive"))
      (node (ref "JP10") (pin "5") (pinfunction "5_5") (pintype "passive"))
      (node (ref "JP11") (pin "5") (pinfunction "5_5") (pintype "passive"))
      (node (ref "JP12") (pin "5") (pinfunction "5_5") (pintype "passive"))
      (node (ref "JP13") (pin "1") (pinfunction "1_1") (pintype "passive"))
      (node (ref "JP2") (pin "5") (pinfunction "5_5") (pintype "passive"))
      (node (ref "JP3") (pin "5") (pinfunction "5_5") (pintype "passive"))
      (node (ref "JP4") (pin "5") (pinfunction "5_5") (pintype "passive"))
      (node (ref "JP5") (pin "5") (pinfunction "5_5") (pintype "passive"))
      (node (ref "JP6") (pin "5") (pinfunction "5_5") (pintype "passive"))
      (node (ref "JP7") (pin "5") (pinfunction "5_5") (pintype "passive"))
      (node (ref "JP8") (pin "5") (pinfunction "5_5") (pintype "passive"))
      (node (ref "JP9") (pin "5") (pinfunction "5_5") (pintype "passive"))
      (node (ref "PCB1") (pin "GND.") (pinfunction "GND._GND.") (pintype "bidirectional"))
      (node (ref "PCB1") (pin "GND..") (pinfunction "GND.._GND..") (pintype "bidirectional"))
      (node (ref "PCB1") (pin "GND...") (pinfunction "GND..._GND...") (pintype "bidirectional"))
      (node (ref "PCB1") (pin "GND....") (pinfunction "GND...._GND....") (pintype "bidirectional"))
      (node (ref "R1") (pin "P$2") (pinfunction "P$2_P$2") (pintype "passive"))
      (node (ref "R10") (pin "P$1") (pinfunction "P$1_P$1") (pintype "passive"))
      (node (ref "R11") (pin "P$1") (pinfunction "P$1_P$1") (pintype "passive"))
      (node (ref "R12") (pin "P$1") (pinfunction "P$1_P$1") (pintype "passive"))
      (node (ref "R2") (pin "P$1") (pinfunction "P$1_P$1") (pintype "passive"))
      (node (ref "R3") (pin "P$2") (pinfunction "P$2_P$2") (pintype "passive"))
      (node (ref "R4") (pin "P$2") (pinfunction "P$2_P$2") (pintype "passive"))
      (node (ref "R5") (pin "P$2") (pinfunction "P$2_P$2") (pintype "passive"))
      (node (ref "R6") (pin "P$2") (pinfunction "P$2_P$2") (pintype "passive"))
      (node (ref "R7") (pin "P$2") (pinfunction "P$2_P$2") (pintype "passive"))
      (node (ref "R8") (pin "P$1") (pinfunction "P$1_P$1") (pintype "passive"))
      (node (ref "R9") (pin "P$1") (pinfunction "P$1_P$1") (pintype "passive"))
    )
    (net (code "76") (name "Net-(PCB1-14(TX3))") (class "Default")
      (node (ref "JP16") (pin "1") (pinfunction "1_1") (pintype "passive"))
      (node (ref "PCB1") (pin "14") (pinfunction "14(TX3)_14") (pintype "bidirectional"))
    )
    (net (code "77") (name "Net-(PCB1-15(RX3))") (class "Default")
      (node (ref "JP16") (pin "2") (pinfunction "2_2") (pintype "passive"))
      (node (ref "PCB1") (pin "15") (pinfunction "15(RX3)_15") (pintype "bidirectional"))
    )
    (net (code "78") (name "Net-(PCB1-16(TX2))") (class "Default")
      (node (ref "JP15") (pin "1") (pinfunction "1_1") (pintype "passive"))
      (node (ref "PCB1") (pin "16") (pinfunction "16(TX2)_16") (pintype "bidirectional"))
    )
    (net (code "79") (name "Net-(PCB1-17(RX2))") (class "Default")
      (node (ref "JP15") (pin "2") (pinfunction "2_2") (pintype "passive"))
      (node (ref "PCB1") (pin "17") (pinfunction "17(RX2)_17") (pintype "bidirectional"))
    )
    (net (code "80") (name "Net-(PCB1-18(TX1))") (class "Default")
      (node (ref "JP14") (pin "1") (pinfunction "1_1") (pintype "passive"))
      (node (ref "PCB1") (pin "18") (pinfunction "18(TX1)_18") (pintype "bidirectional"))
    )
    (net (code "81") (name "Net-(PCB1-19(RX1))") (class "Default")
      (node (ref "JP14") (pin "2") (pinfunction "2_2") (pintype "passive"))
      (node (ref "PCB1") (pin "19") (pinfunction "19(RX1)_19") (pintype "bidirectional"))
    )
    (net (code "82") (name "unconnected-(PCB1-+5V.-Pad5V.)") (class "Default")
      (node (ref "PCB1") (pin "5V.") (pinfunction "+5V._5V.") (pintype "bidirectional"))
    )
    (net (code "83") (name "unconnected-(PCB1-+5V..-Pad5V..)") (class "Default")
      (node (ref "PCB1") (pin "5V..") (pinfunction "+5V.._5V..") (pintype "bidirectional"))
    )
    (net (code "84") (name "unconnected-(PCB1-0(RX)-Pad0)") (class "Default")
      (node (ref "PCB1") (pin "0") (pinfunction "0(RX)_0") (pintype "bidirectional"))
    )
    (net (code "85") (name "unconnected-(PCB1-1(TX)-Pad1)") (class "Default")
      (node (ref "PCB1") (pin "1") (pinfunction "1(TX)_1") (pintype "bidirectional"))
    )
    (net (code "86") (name "unconnected-(PCB1-20(SDA)-Pad20)") (class "Default")
      (node (ref "PCB1") (pin "20") (pinfunction "20(SDA)_20") (pintype "bidirectional"))
    )
    (net (code "87") (name "unconnected-(PCB1-21(SCL)-Pad21)") (class "Default")
      (node (ref "PCB1") (pin "21") (pinfunction "21(SCL)_21") (pintype "bidirectional"))
    )
    (net (code "88") (name "unconnected-(PCB1-Pad3.3V)") (class "Default")
      (node (ref "PCB1") (pin "3.3V") (pinfunction "3.3V_3.3V") (pintype "bidirectional"))
    )
    (net (code "89") (name "unconnected-(PCB1-Pad13)") (class "Default")
      (node (ref "PCB1") (pin "13") (pinfunction "13_13") (pintype "bidirectional"))
    )
    (net (code "90") (name "unconnected-(PCB1-Pad22)") (class "Default")
      (node (ref "PCB1") (pin "22") (pinfunction "22_22") (pintype "bidirectional"))
    )
    (net (code "91") (name "unconnected-(PCB1-Pad23)") (class "Default")
      (node (ref "PCB1") (pin "23") (pinfunction "23_23") (pintype "bidirectional"))
    )
    (net (code "92") (name "unconnected-(PCB1-Pad24)") (class "Default")
      (node (ref "PCB1") (pin "24") (pinfunction "24_24") (pintype "bidirectional"))
    )
    (net (code "93") (name "unconnected-(PCB1-Pad25)") (class "Default")
      (node (ref "PCB1") (pin "25") (pinfunction "25_25") (pintype "bidirectional"))
    )
    (net (code "94") (name "unconnected-(PCB1-Pad26)") (class "Default")
      (node (ref "PCB1") (pin "26") (pinfunction "26_26") (pintype "bidirectional"))
    )
    (net (code "95") (name "unconnected-(PCB1-Pad27)") (class "Default")
      (node (ref "PCB1") (pin "27") (pinfunction "27_27") (pintype "bidirectional"))
    )
    (net (code "96") (name "unconnected-(PCB1-Pad28)") (class "Default")
      (node (ref "PCB1") (pin "28") (pinfunction "28_28") (pintype "bidirectional"))
    )
    (net (code "97") (name "unconnected-(PCB1-Pad29)") (class "Default")
      (node (ref "PCB1") (pin "29") (pinfunction "29_29") (pintype "bidirectional"))
    )
    (net (code "98") (name "unconnected-(PCB1-Pad31)") (class "Default")
      (node (ref "PCB1") (pin "31") (pinfunction "31_31") (pintype "bidirectional"))
    )
    (net (code "99") (name "unconnected-(PCB1-Pad33)") (class "Default")
      (node (ref "PCB1") (pin "33") (pinfunction "33_33") (pintype "bidirectional"))
    )
    (net (code "100") (name "unconnected-(PCB1-Pad35)") (class "Default")
      (node (ref "PCB1") (pin "35") (pinfunction "35_35") (pintype "bidirectional"))
    )
    (net (code "101") (name "unconnected-(PCB1-Pad37)") (class "Default")
      (node (ref "PCB1") (pin "37") (pinfunction "37_37") (pintype "bidirectional"))
    )
    (net (code "102") (name "unconnected-(PCB1-Pad39)") (class "Default")
      (node (ref "PCB1") (pin "39") (pinfunction "39_39") (pintype "bidirectional"))
    )
    (net (code "103") (name "unconnected-(PCB1-Pad41)") (class "Default")
      (node (ref "PCB1") (pin "41") (pinfunction "41_41") (pintype "bidirectional"))
    )
    (net (code "104") (name "unconnected-(PCB1-Pad43)") (class "Default")
      (node (ref "PCB1") (pin "43") (pinfunction "43_43") (pintype "bidirectional"))
    )
    (net (code "105") (name "unconnected-(PCB1-Pad47)") (class "Default")
      (node (ref "PCB1") (pin "47") (pinfunction "47_47") (pintype "bidirectional"))
    )
    (net (code "106") (name "unconnected-(PCB1-Pad49)") (class "Default")
      (node (ref "PCB1") (pin "49") (pinfunction "49_49") (pintype "bidirectional"))
    )
    (net (code "107") (name "unconnected-(PCB1-Pad51)") (class "Default")
      (node (ref "PCB1") (pin "51") (pinfunction "51_51") (pintype "bidirectional"))
    )
    (net (code "108") (name "unconnected-(PCB1-Pad53)") (class "Default")
      (node (ref "PCB1") (pin "53") (pinfunction "53_53") (pintype "bidirectional"))
    )
    (net (code "109") (name "unconnected-(PCB1-PadA12)") (class "Default")
      (node (ref "PCB1") (pin "A12") (pinfunction "A12_A12") (pintype "bidirectional"))
    )
    (net (code "110") (name "unconnected-(PCB1-PadA13)") (class "Default")
      (node (ref "PCB1") (pin "A13") (pinfunction "A13_A13") (pintype "bidirectional"))
    )
    (net (code "111") (name "unconnected-(PCB1-PadA14)") (class "Default")
      (node (ref "PCB1") (pin "A14") (pinfunction "A14_A14") (pintype "bidirectional"))
    )
    (net (code "112") (name "unconnected-(PCB1-PadA15)") (class "Default")
      (node (ref "PCB1") (pin "A15") (pinfunction "A15_A15") (pintype "bidirectional"))
    )
    (net (code "113") (name "unconnected-(PCB1-PadAREF)") (class "Default")
      (node (ref "PCB1") (pin "AREF") (pinfunction "AREF_AREF") (pintype "bidirectional"))
    )
    (net (code "114") (name "unconnected-(PCB1-PadGND)") (class "Default")
      (node (ref "PCB1") (pin "GND") (pinfunction "GND_GND") (pintype "bidirectional"))
    )
    (net (code "115") (name "unconnected-(PCB1-PadRESET)") (class "Default")
      (node (ref "PCB1") (pin "RESET") (pinfunction "RESET_RESET") (pintype "bidirectional"))
    )
    (net (code "116") (name "unconnected-(PCB1-PadSCL1)") (class "Default")
      (node (ref "PCB1") (pin "SCL1") (pinfunction "SCL1_SCL1") (pintype "bidirectional"))
    )
    (net (code "117") (name "unconnected-(PCB1-PadSDA1)") (class "Default")
      (node (ref "PCB1") (pin "SDA1") (pinfunction "SDA1_SDA1") (pintype "bidirectional"))
    )
  )
)
